# main.net
KiCad netlist of a schematic drawn in EAGLE
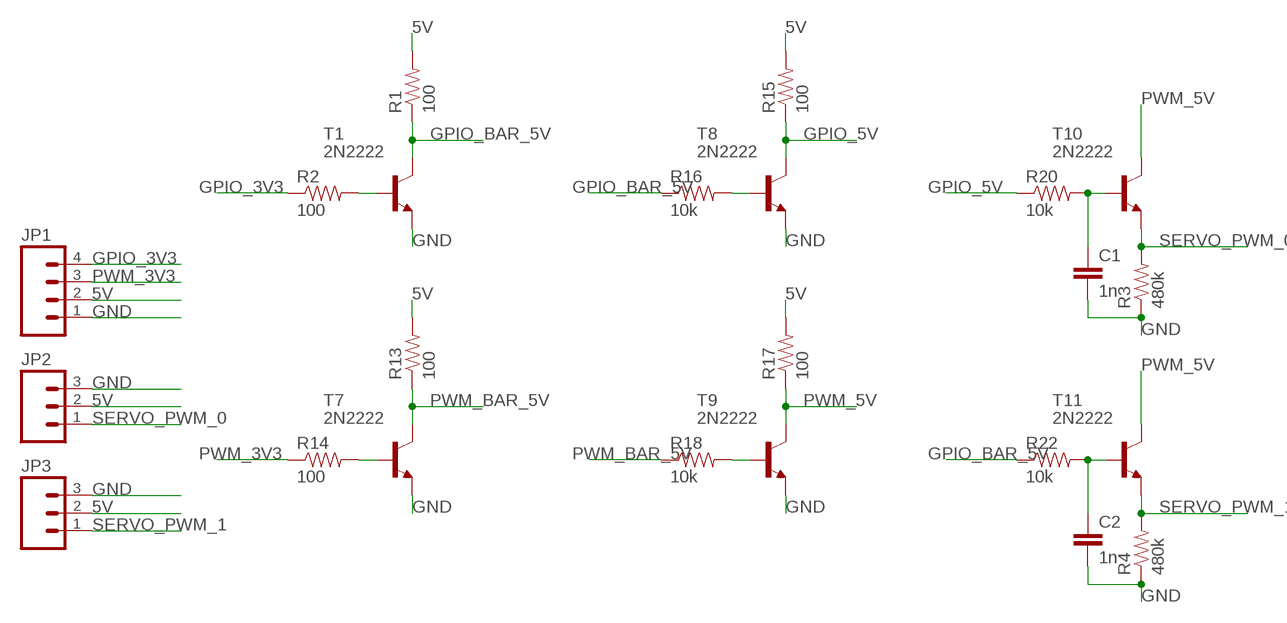
[diagram p0: schematic, sheet 1]

(export (version "E")
  (design (tool "Eeschema 10.0.6"))
  (components
    (comp (ref "C1")
      (value "1n")
      (footprint "eagle-import:CAP-PTH-SMALL-KIT")
      (libsource (lib "eagle-import") (part "CAPKIT"))
    )
    (comp (ref "C2")
      (value "1n")
      (footprint "eagle-import:CAP-PTH-SMALL-KIT")
      (libsource (lib "eagle-import") (part "CAPKIT"))
    )
    (comp (ref "JP1")
      (value "M04LONGPADS")
      (footprint "eagle-import:1X04_LONGPADS")
      (libsource (lib "eagle-import") (part "M04LONGPADS"))
    )
    (comp (ref "JP2")
      (value "M03LONGPADS")
      (footprint "eagle-import:1X03_LONGPADS")
      (libsource (lib "eagle-import") (part "M03LONGPADS"))
    )
    (comp (ref "JP3")
      (value "M03LONGPADS")
      (footprint "eagle-import:1X03_LONGPADS")
      (libsource (lib "eagle-import") (part "M03LONGPADS"))
    )
    (comp (ref "R1")
      (value "100")
      (footprint "eagle-import:AXIAL-0.4")
      (libsource (lib "eagle-import") (part "RESISTORPTH-1/4W"))
    )
    (comp (ref "R2")
      (value "100")
      (footprint "eagle-import:AXIAL-0.4")
      (libsource (lib "eagle-import") (part "RESISTORPTH-1/4W"))
    )
    (comp (ref "R3")
      (value "480k")
      (footprint "eagle-import:AXIAL-0.4")
      (libsource (lib "eagle-import") (part "RESISTORPTH-1/4W"))
    )
    (comp (ref "R4")
      (value "480k")
      (footprint "eagle-import:AXIAL-0.4")
      (libsource (lib "eagle-import") (part "RESISTORPTH-1/4W"))
    )
    (comp (ref "R13")
      (value "100")
      (footprint "eagle-import:AXIAL-0.4")
      (libsource (lib "eagle-import") (part "RESISTORPTH-1/4W"))
    )
    (comp (ref "R14")
      (value "100")
      (footprint "eagle-import:AXIAL-0.4")
      (libsource (lib "eagle-import") (part "RESISTORPTH-1/4W"))
    )
    (comp (ref "R15")
      (value "100")
      (footprint "eagle-import:AXIAL-0.4")
      (libsource (lib "eagle-import") (part "RESISTORPTH-1/4W"))
    )
    (comp (ref "R16")
      (value "10k")
      (footprint "eagle-import:AXIAL-0.4")
      (libsource (lib "eagle-import") (part "RESISTORPTH-1/4W"))
    )
    (comp (ref "R17")
      (value "100")
      (footprint "eagle-import:AXIAL-0.4")
      (libsource (lib "eagle-import") (part "RESISTORPTH-1/4W"))
    )
    (comp (ref "R18")
      (value "10k")
      (footprint "eagle-import:AXIAL-0.4")
      (libsource (lib "eagle-import") (part "RESISTORPTH-1/4W"))
    )
    (comp (ref "R20")
      (value "10k")
      (footprint "eagle-import:AXIAL-0.4")
      (libsource (lib "eagle-import") (part "RESISTORPTH-1/4W"))
    )
    (comp (ref "R22")
      (value "10k")
      (footprint "eagle-import:AXIAL-0.4")
      (libsource (lib "eagle-import") (part "RESISTORPTH-1/4W"))
    )
    (comp (ref "T1")
      (value "2N2222")
      (footprint "eagle-import:TO18")
      (libsource (lib "eagle-import") (part "2N2222"))
    )
    (comp (ref "T7")
      (value "2N2222")
      (footprint "eagle-import:TO18")
      (libsource (lib "eagle-import") (part "2N2222"))
    )
    (comp (ref "T8")
      (value "2N2222")
      (footprint "eagle-import:TO18")
      (libsource (lib "eagle-import") (part "2N2222"))
    )
    (comp (ref "T9")
      (value "2N2222")
      (footprint "eagle-import:TO18")
      (libsource (lib "eagle-import") (part "2N2222"))
    )
    (comp (ref "T10")
      (value "2N2222")
      (footprint "eagle-import:TO18")
      (libsource (lib "eagle-import") (part "2N2222"))
    )
    (comp (ref "T11")
      (value "2N2222")
      (footprint "eagle-import:TO18")
      (libsource (lib "eagle-import") (part "2N2222"))
    )
  )
  (nets
    (net (code "1") (name "/5V") (class "Default")
      (node (ref "JP1") (pin "2") (pinfunction "2_2") (pintype "passive"))
      (node (ref "JP2") (pin "2") (pinfunction "2_2") (pintype "passive"))
      (node (ref "JP3") (pin "2") (pinfunction "2_2") (pintype "passive"))
      (node (ref "R1") (pin "P$2") (pinfunction "2_P$2") (pintype "passive"))
      (node (ref "R13") (pin "P$2") (pinfunction "2_P$2") (pintype "passive"))
      (node (ref "R15") (pin "P$2") (pinfunction "2_P$2") (pintype "passive"))
      (node (ref "R17") (pin "P$2") (pinfunction "2_P$2") (pintype "passive"))
    )
    (net (code "2") (name "/GND") (class "Default")
      (node (ref "C1") (pin "2") (pinfunction "2_2") (pintype "passive"))
      (node (ref "C2") (pin "2") (pinfunction "2_2") (pintype "passive"))
      (node (ref "JP1") (pin "1") (pinfunction "1_1") (pintype "passive"))
      (node (ref "JP2") (pin "3") (pinfunction "3_3") (pintype "passive"))
      (node (ref "JP3") (pin "3") (pinfunction "3_3") (pintype "passive"))
      (node (ref "R3") (pin "P$1") (pinfunction "1_P$1") (pintype "passive"))
      (node (ref "R4") (pin "P$1") (pinfunction "1_P$1") (pintype "passive"))
      (node (ref "T1") (pin "1") (pinfunction "E_1") (pintype "passive"))
      (node (ref "T7") (pin "1") (pinfunction "E_1") (pintype "passive"))
      (node (ref "T8") (pin "1") (pinfunction "E_1") (pintype "passive"))
      (node (ref "T9") (pin "1") (pinfunction "E_1") (pintype "passive"))
    )
    (net (code "3") (name "/GPIO_3V3") (class "Default")
      (node (ref "JP1") (pin "4") (pinfunction "4_4") (pintype "passive"))
      (node (ref "R2") (pin "P$1") (pinfunction "1_P$1") (pintype "passive"))
    )
    (net (code "4") (name "/GPIO_5V") (class "Default")
      (node (ref "R15") (pin "P$1") (pinfunction "1_P$1") (pintype "passive"))
      (node (ref "R20") (pin "P$1") (pinfunction "1_P$1") (pintype "passive"))
      (node (ref "T8") (pin "3") (pinfunction "C_3") (pintype "passive"))
    )
    (net (code "5") (name "/GPIO_BAR_5V") (class "Default")
      (node (ref "R1") (pin "P$1") (pinfunction "1_P$1") (pintype "passive"))
      (node (ref "R16") (pin "P$1") (pinfunction "1_P$1") (pintype "passive"))
      (node (ref "R22") (pin "P$1") (pinfunction "1_P$1") (pintype "passive"))
      (node (ref "T1") (pin "3") (pinfunction "C_3") (pintype "passive"))
    )
    (net (code "6") (name "/PWM_3V3") (class "Default")
      (node (ref "JP1") (pin "3") (pinfunction "3_3") (pintype "passive"))
      (node (ref "R14") (pin "P$1") (pinfunction "1_P$1") (pintype "passive"))
    )
    (net (code "7") (name "/PWM_5V") (class "Default")
      (node (ref "R17") (pin "P$1") (pinfunction "1_P$1") (pintype "passive"))
      (node (ref "T10") (pin "3") (pinfunction "C_3") (pintype "passive"))
      (node (ref "T11") (pin "3") (pinfunction "C_3") (pintype "passive"))
      (node (ref "T9") (pin "3") (pinfunction "C_3") (pintype "passive"))
    )
    (net (code "8") (name "/PWM_BAR_5V") (class "Default")
      (node (ref "R13") (pin "P$1") (pinfunction "1_P$1") (pintype "passive"))
      (node (ref "R18") (pin "P$1") (pinfunction "1_P$1") (pintype "passive"))
      (node (ref "T7") (pin "3") (pinfunction "C_3") (pintype "passive"))
    )
    (net (code "9") (name "/SERVO_PWM_0") (class "Default")
      (node (ref "JP2") (pin "1") (pinfunction "1_1") (pintype "passive"))
      (node (ref "R3") (pin "P$2") (pinfunction "2_P$2") (pintype "passive"))
      (node (ref "T10") (pin "1") (pinfunction "E_1") (pintype "passive"))
    )
    (net (code "10") (name "/SERVO_PWM_1") (class "Default")
      (node (ref "JP3") (pin "1") (pinfunction "1_1") (pintype "passive"))
      (node (ref "R4") (pin "P$2") (pinfunction "2_P$2") (pintype "passive"))
      (node (ref "T11") (pin "1") (pinfunction "E_1") (pintype "passive"))
    )
    (net (code "11") (name "Net-(R2-2)") (class "Default")
      (node (ref "R2") (pin "P$2") (pinfunction "2_P$2") (pintype "passive"))
      (node (ref "T1") (pin "2") (pinfunction "B_2") (pintype "passive"))
    )
    (net (code "12") (name "Net-(R14-2)") (class "Default")
      (node (ref "R14") (pin "P$2") (pinfunction "2_P$2") (pintype "passive"))
      (node (ref "T7") (pin "2") (pinfunction "B_2") (pintype "passive"))
    )
    (net (code "13") (name "Net-(R16-2)") (class "Default")
      (node (ref "R16") (pin "P$2") (pinfunction "2_P$2") (pintype "passive"))
      (node (ref "T8") (pin "2") (pinfunction "B_2") (pintype "passive"))
    )
    (net (code "14") (name "Net-(R18-2)") (class "Default")
      (node (ref "R18") (pin "P$2") (pinfunction "2_P$2") (pintype "passive"))
      (node (ref "T9") (pin "2") (pinfunction "B_2") (pintype "passive"))
    )
    (net (code "15") (name "Net-(R20-2)") (class "Default")
      (node (ref "C1") (pin "1") (pinfunction "1_1") (pintype "passive"))
      (node (ref "R20") (pin "P$2") (pinfunction "2_P$2") (pintype "passive"))
      (node (ref "T10") (pin "2") (pinfunction "B_2") (pintype "passive"))
    )
    (net (code "16") (name "Net-(R22-2)") (class "Default")
      (node (ref "C2") (pin "1") (pinfunction "1_1") (pintype "passive"))
      (node (ref "R22") (pin "P$2") (pinfunction "2_P$2") (pintype "passive"))
      (node (ref "T11") (pin "2") (pinfunction "B_2") (pintype "passive"))
    )
  )
)
